# ubadge.net
KiCad netlist of a schematic drawn in EAGLE
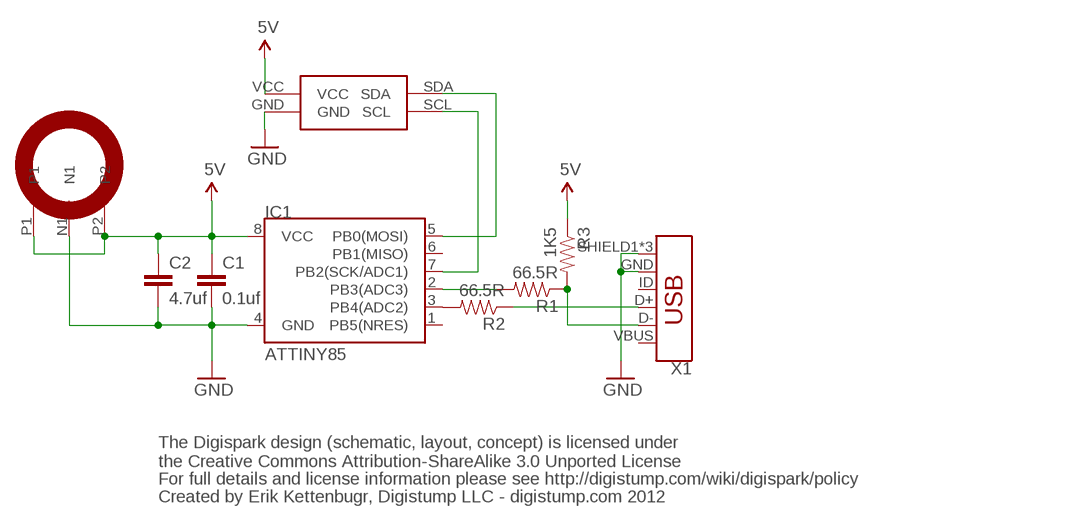
[diagram p0: schematic, sheet 1]

(export (version "E")
  (design (tool "Eeschema 10.0.6"))
  (components
    (comp (ref "C1")
      (value "0.1uf")
      (footprint "eagle-import:0402-CAP")
      (libsource (lib "eagle-import") (part "CAP0402-CAP"))
    )
    (comp (ref "C2")
      (value "4.7uf")
      (footprint "eagle-import:0805")
      (libsource (lib "eagle-import") (part "CAP0805"))
    )
    (comp (ref "IC1")
      (value "ATTINY85")
      (footprint "eagle-import:SO08-EIAJ")
      (libsource (lib "eagle-import") (part "ATTINY45"))
    )
    (comp (ref "R1")
      (value "66.5R")
      (footprint "eagle-import:0402-RES")
      (libsource (lib "eagle-import") (part "RESISTOR0402-RES"))
    )
    (comp (ref "R2")
      (value "66.5R")
      (footprint "eagle-import:0402-RES")
      (libsource (lib "eagle-import") (part "RESISTOR0402-RES"))
    )
    (comp (ref "R3")
      (value "1K5")
      (footprint "eagle-import:0402-RES")
      (libsource (lib "eagle-import") (part "RESISTOR0402-RES"))
    )
    (comp (ref "U$1")
      (value "SAO-SMT-BOARD")
      (footprint "eagle-import:SAO-SMD-BADGE-SOCKET")
      (libsource (lib "eagle-import") (part "SAO-SMT-BOARD"))
    )
    (comp (ref "U$2")
      (value "CR2032-VERT")
      (footprint "eagle-import:CR2032-VERT")
      (libsource (lib "eagle-import") (part "CR2032-VERT"))
    )
    (comp (ref "X1")
      (value "USB_MICRO-B_FEMALE-SMT")
      (footprint "eagle-import:USB-B-MICRO-SMD")
      (libsource (lib "eagle-import") (part "USB_MICRO-B_FEMALE-SMT"))
    )
  )
  (nets
    (net (code "1") (name "/VBUS") (class "Default")
      (node (ref "X1") (pin "VBUS") (pinfunction "VBUS_VBUS") (pintype "power_in"))
    )
    (net (code "2") (name "5V") (class "Default")
      (node (ref "C1") (pin "1") (pinfunction "1_1") (pintype "passive"))
      (node (ref "C2") (pin "1") (pinfunction "1_1") (pintype "passive"))
      (node (ref "IC1") (pin "8") (pinfunction "VCC_8") (pintype "bidirectional"))
      (node (ref "R3") (pin "1") (pinfunction "1_1") (pintype "passive"))
      (node (ref "U$1") (pin "VCC") (pinfunction "VCC_VCC") (pintype "bidirectional"))
      (node (ref "U$2") (pin "P1") (pinfunction "P1_P1") (pintype "bidirectional"))
      (node (ref "U$2") (pin "P2") (pinfunction "P2_P2") (pintype "bidirectional"))
    )
    (net (code "3") (name "GND") (class "Default")
      (node (ref "C1") (pin "2") (pinfunction "2_2") (pintype "passive"))
      (node (ref "C2") (pin "2") (pinfunction "2_2") (pintype "passive"))
      (node (ref "IC1") (pin "4") (pinfunction "GND_4") (pintype "bidirectional"))
      (node (ref "U$1") (pin "GND") (pinfunction "GND_GND") (pintype "bidirectional"))
      (node (ref "U$2") (pin "N1") (pinfunction "N1_N1") (pintype "bidirectional"))
      (node (ref "X1") (pin "GND") (pinfunction "GND_GND") (pintype "power_in"))
      (node (ref "X1") (pin "SHIELD1") (pinfunction "SHIELD_SHIELD1") (pintype "bidirectional"))
      (node (ref "X1") (pin "SHIELD2") (pinfunction "SHIELD_SHIELD2") (pintype "bidirectional"))
      (node (ref "X1") (pin "SHIELD3") (pinfunction "SHIELD_SHIELD3") (pintype "bidirectional"))
    )
    (net (code "4") (name "Net-(IC1-PB0(MOSI))") (class "Default")
      (node (ref "IC1") (pin "5") (pinfunction "PB0(MOSI)_5") (pintype "bidirectional"))
      (node (ref "U$1") (pin "SDA") (pinfunction "SDA_SDA") (pintype "bidirectional"))
    )
    (net (code "5") (name "Net-(IC1-PB2(SCK{slash}ADC1))") (class "Default")
      (node (ref "IC1") (pin "7") (pinfunction "PB2(SCK/ADC1)_7") (pintype "bidirectional"))
      (node (ref "U$1") (pin "SCL") (pinfunction "SCL_SCL") (pintype "bidirectional"))
    )
    (net (code "6") (name "Net-(IC1-PB3(ADC3))") (class "Default")
      (node (ref "IC1") (pin "2") (pinfunction "PB3(ADC3)_2") (pintype "bidirectional"))
      (node (ref "R1") (pin "2") (pinfunction "2_2") (pintype "passive"))
    )
    (net (code "7") (name "Net-(IC1-PB4(ADC2))") (class "Default")
      (node (ref "IC1") (pin "3") (pinfunction "PB4(ADC2)_3") (pintype "bidirectional"))
      (node (ref "R2") (pin "2") (pinfunction "2_2") (pintype "passive"))
    )
    (net (code "8") (name "Net-(R1-Pad1)") (class "Default")
      (node (ref "R1") (pin "1") (pinfunction "1_1") (pintype "passive"))
      (node (ref "R3") (pin "2") (pinfunction "2_2") (pintype "passive"))
      (node (ref "X1") (pin "D-") (pinfunction "D-_D-") (pintype "bidirectional"))
    )
    (net (code "9") (name "Net-(R2-Pad1)") (class "Default")
      (node (ref "R2") (pin "1") (pinfunction "1_1") (pintype "passive"))
      (node (ref "X1") (pin "D+") (pinfunction "D+_D+") (pintype "bidirectional"))
    )
    (net (code "10") (name "unconnected-(IC1-PB1(MISO)-Pad6)") (class "Default")
      (node (ref "IC1") (pin "6") (pinfunction "PB1(MISO)_6") (pintype "bidirectional"))
    )
    (net (code "11") (name "unconnected-(IC1-PB5(NRES)-Pad1)") (class "Default")
      (node (ref "IC1") (pin "1") (pinfunction "PB5(NRES)_1") (pintype "bidirectional"))
    )
    (net (code "12") (name "unconnected-(X1-PadID)") (class "Default")
      (node (ref "X1") (pin "ID") (pinfunction "ID_ID") (pintype "bidirectional"))
    )
  )
)
